# Connectors.net
KiCad netlist of a schematic drawn in Altium Designer
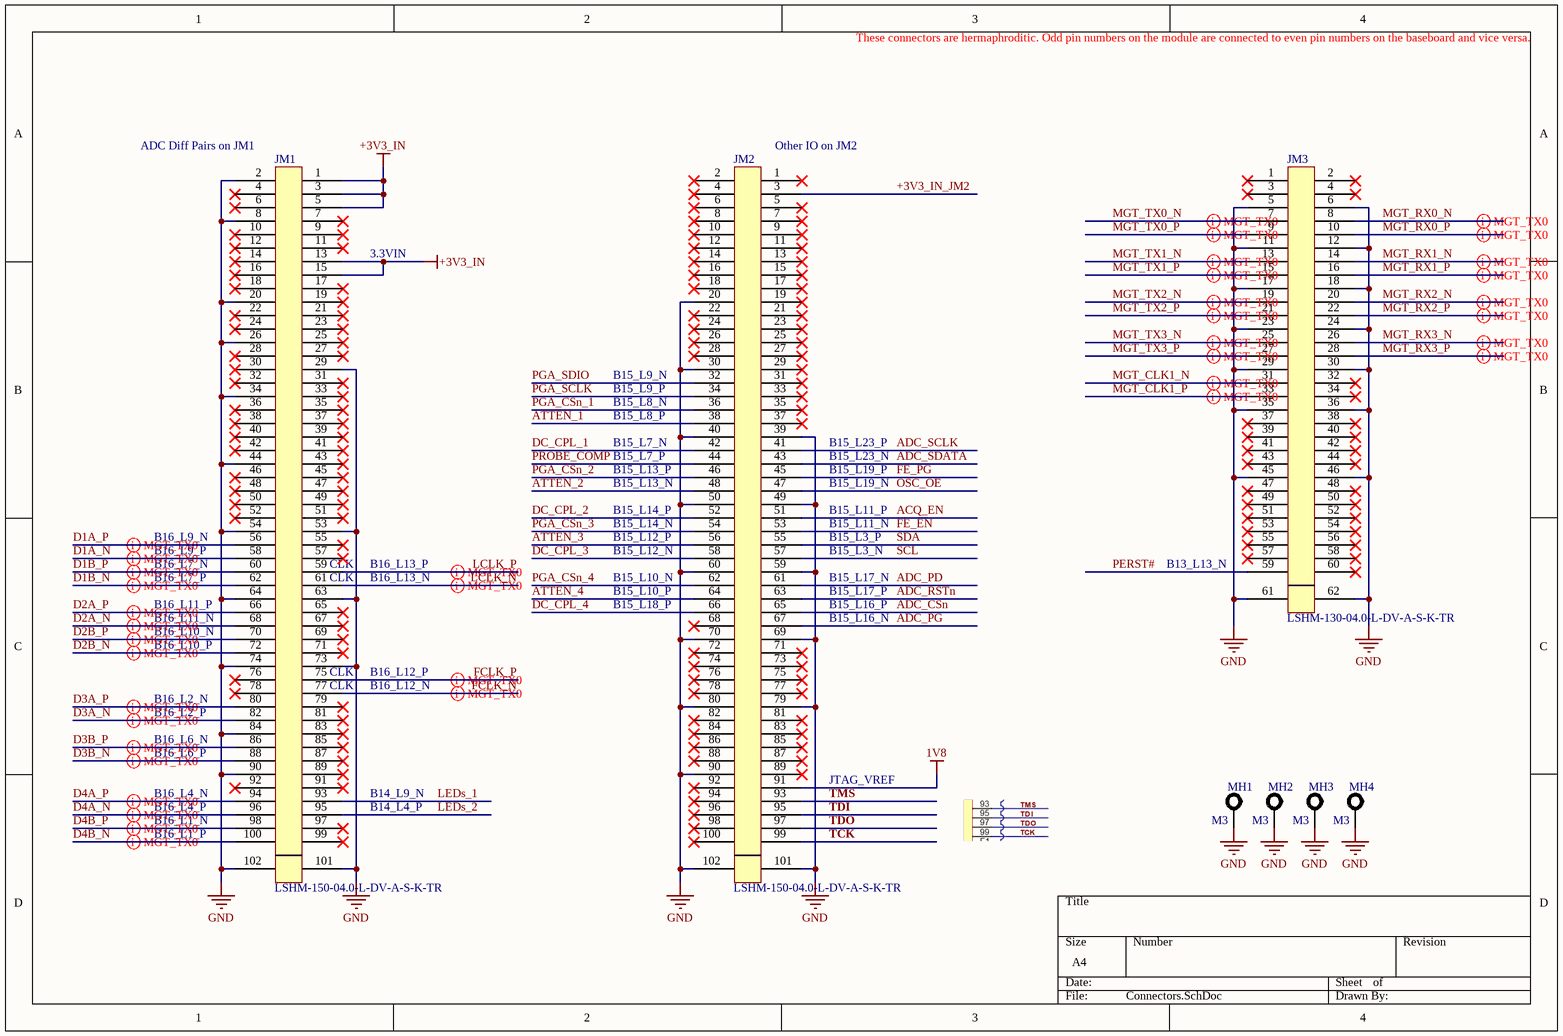
[diagram p0: Connectors.SchDoc]

(export (version "E")
  (design (tool "Eeschema 10.0.6"))
  (components
    (comp (ref "JM1")
      (value "LSHM-150-04.0-L-DV-A-S-K-TR")
      (footprint "SAM_LSHM-150-XX.X-XX-DV-A-S")
      (libsource (lib "DSO") (part "CONN LSHM-150-04.0-L-DV-A-S-K-TR"))
    )
    (comp (ref "JM2")
      (value "LSHM-150-04.0-L-DV-A-S-K-TR")
      (footprint "SAM_LSHM-150-XX.X-XX-DV-A-S")
      (libsource (lib "DSO") (part "CONN LSHM-150-04.0-L-DV-A-S-K-TR"))
    )
    (comp (ref "JM3")
      (value "LSHM-130-04.0-L-DV-A-S-K-TR")
      (footprint "SAM_LSHM-130-XX.X-XX-DV-A-S")
      (libsource (lib "DSO") (part "CONN LSHM-130-04.0-L-DV-A-S-K-TR"))
    )
    (comp (ref "MH1") (value "M3") (footprint "MH M3") (libsource (lib "DSO") (part "MH M3")))
    (comp (ref "MH2") (value "M3") (footprint "MH M3") (libsource (lib "DSO") (part "MH M3")))
    (comp (ref "MH3") (value "M3") (footprint "MH M3") (libsource (lib "DSO") (part "MH M3")))
    (comp (ref "MH4") (value "M3") (footprint "MH M3") (libsource (lib "DSO") (part "MH M3")))
  )
  (nets
    (net (code "1") (name "+3V3_IN") (class "Default")
      (node (ref "JM1") (pin "1") (pinfunction "1_1") (pintype "passive"))
      (node (ref "JM1") (pin "13") (pinfunction "13_13") (pintype "passive"))
      (node (ref "JM1") (pin "15") (pinfunction "15_15") (pintype "passive"))
      (node (ref "JM1") (pin "3") (pinfunction "3_3") (pintype "passive"))
      (node (ref "JM1") (pin "5") (pinfunction "5_5") (pintype "passive"))
    )
    (net (code "2") (name "/+3V3_IN_JM2") (class "Default")
      (node (ref "JM2") (pin "3") (pinfunction "3_3") (pintype "passive"))
    )
    (net (code "3") (name "/ACQ_EN") (class "Default")
      (node (ref "JM2") (pin "51") (pinfunction "51_51") (pintype "passive"))
    )
    (net (code "4") (name "/ADC_CSn") (class "Default")
      (node (ref "JM2") (pin "65") (pinfunction "65_65") (pintype "passive"))
    )
    (net (code "5") (name "/ADC_PD") (class "Default")
      (node (ref "JM2") (pin "61") (pinfunction "61_61") (pintype "passive"))
    )
    (net (code "6") (name "/ADC_PG") (class "Default")
      (node (ref "JM2") (pin "67") (pinfunction "67_67") (pintype "passive"))
    )
    (net (code "7") (name "/ADC_RSTn") (class "Default")
      (node (ref "JM2") (pin "63") (pinfunction "63_63") (pintype "passive"))
    )
    (net (code "8") (name "/ADC_SCLK") (class "Default")
      (node (ref "JM2") (pin "41") (pinfunction "41_41") (pintype "passive"))
    )
    (net (code "9") (name "/ADC_SDATA") (class "Default")
      (node (ref "JM2") (pin "43") (pinfunction "43_43") (pintype "passive"))
    )
    (net (code "10") (name "/ATTEN_1") (class "Default")
      (node (ref "JM2") (pin "38") (pinfunction "38_38") (pintype "passive"))
    )
    (net (code "11") (name "/ATTEN_2") (class "Default")
      (node (ref "JM2") (pin "48") (pinfunction "48_48") (pintype "passive"))
    )
    (net (code "12") (name "/ATTEN_3") (class "Default")
      (node (ref "JM2") (pin "56") (pinfunction "56_56") (pintype "passive"))
    )
    (net (code "13") (name "/ATTEN_4") (class "Default")
      (node (ref "JM2") (pin "64") (pinfunction "64_64") (pintype "passive"))
    )
    (net (code "14") (name "/D1A_N") (class "Default")
      (node (ref "JM1") (pin "58") (pinfunction "58_58") (pintype "passive"))
    )
    (net (code "15") (name "/D1A_P") (class "Default")
      (node (ref "JM1") (pin "56") (pinfunction "56_56") (pintype "passive"))
    )
    (net (code "16") (name "/D1B_N") (class "Default")
      (node (ref "JM1") (pin "62") (pinfunction "62_62") (pintype "passive"))
    )
    (net (code "17") (name "/D1B_P") (class "Default")
      (node (ref "JM1") (pin "60") (pinfunction "60_60") (pintype "passive"))
    )
    (net (code "18") (name "/D2A_N") (class "Default")
      (node (ref "JM1") (pin "68") (pinfunction "68_68") (pintype "passive"))
    )
    (net (code "19") (name "/D2A_P") (class "Default")
      (node (ref "JM1") (pin "66") (pinfunction "66_66") (pintype "passive"))
    )
    (net (code "20") (name "/D2B_N") (class "Default")
      (node (ref "JM1") (pin "72") (pinfunction "72_72") (pintype "passive"))
    )
    (net (code "21") (name "/D2B_P") (class "Default")
      (node (ref "JM1") (pin "70") (pinfunction "70_70") (pintype "passive"))
    )
    (net (code "22") (name "/D3A_N") (class "Default")
      (node (ref "JM1") (pin "82") (pinfunction "82_82") (pintype "passive"))
    )
    (net (code "23") (name "/D3A_P") (class "Default")
      (node (ref "JM1") (pin "80") (pinfunction "80_80") (pintype "passive"))
    )
    (net (code "24") (name "/D3B_N") (class "Default")
      (node (ref "JM1") (pin "88") (pinfunction "88_88") (pintype "passive"))
    )
    (net (code "25") (name "/D3B_P") (class "Default")
      (node (ref "JM1") (pin "86") (pinfunction "86_86") (pintype "passive"))
    )
    (net (code "26") (name "/D4A_N") (class "Default")
      (node (ref "JM1") (pin "96") (pinfunction "96_96") (pintype "passive"))
    )
    (net (code "27") (name "/D4A_P") (class "Default")
      (node (ref "JM1") (pin "94") (pinfunction "94_94") (pintype "passive"))
    )
    (net (code "28") (name "/D4B_N") (class "Default")
      (node (ref "JM1") (pin "100") (pinfunction "100_100") (pintype "passive"))
    )
    (net (code "29") (name "/D4B_P") (class "Default")
      (node (ref "JM1") (pin "98") (pinfunction "98_98") (pintype "passive"))
    )
    (net (code "30") (name "/DC_CPL_1") (class "Default")
      (node (ref "JM2") (pin "42") (pinfunction "42_42") (pintype "passive"))
    )
    (net (code "31") (name "/DC_CPL_2") (class "Default")
      (node (ref "JM2") (pin "52") (pinfunction "52_52") (pintype "passive"))
    )
    (net (code "32") (name "/DC_CPL_3") (class "Default")
      (node (ref "JM2") (pin "58") (pinfunction "58_58") (pintype "passive"))
    )
    (net (code "33") (name "/DC_CPL_4") (class "Default")
      (node (ref "JM2") (pin "66") (pinfunction "66_66") (pintype "passive"))
    )
    (net (code "34") (name "/FCLK_N") (class "Default")
      (node (ref "JM1") (pin "77") (pinfunction "77_77") (pintype "passive"))
    )
    (net (code "35") (name "/FCLK_P") (class "Default")
      (node (ref "JM1") (pin "75") (pinfunction "75_75") (pintype "passive"))
    )
    (net (code "36") (name "/FE_EN") (class "Default")
      (node (ref "JM2") (pin "53") (pinfunction "53_53") (pintype "passive"))
    )
    (net (code "37") (name "/FE_PG") (class "Default")
      (node (ref "JM2") (pin "45") (pinfunction "45_45") (pintype "passive"))
    )
    (net (code "38") (name "/LCLK_N") (class "Default")
      (node (ref "JM1") (pin "61") (pinfunction "61_61") (pintype "passive"))
    )
    (net (code "39") (name "/LCLK_P") (class "Default")
      (node (ref "JM1") (pin "59") (pinfunction "59_59") (pintype "passive"))
    )
    (net (code "40") (name "/LEDs_1") (class "Default")
      (node (ref "JM1") (pin "93") (pinfunction "93_93") (pintype "passive"))
    )
    (net (code "41") (name "/LEDs_2") (class "Default")
      (node (ref "JM1") (pin "95") (pinfunction "95_95") (pintype "passive"))
    )
    (net (code "42") (name "/MGT_CLK1_N") (class "Default")
      (node (ref "JM3") (pin "31") (pinfunction "31_31") (pintype "passive"))
    )
    (net (code "43") (name "/MGT_CLK1_P") (class "Default")
      (node (ref "JM3") (pin "33") (pinfunction "33_33") (pintype "passive"))
    )
    (net (code "44") (name "/MGT_RX0_N") (class "Default")
      (node (ref "JM3") (pin "8") (pinfunction "8_8") (pintype "passive"))
    )
    (net (code "45") (name "/MGT_RX0_P") (class "Default")
      (node (ref "JM3") (pin "10") (pinfunction "10_10") (pintype "passive"))
    )
    (net (code "46") (name "/MGT_RX1_N") (class "Default")
      (node (ref "JM3") (pin "14") (pinfunction "14_14") (pintype "passive"))
    )
    (net (code "47") (name "/MGT_RX1_P") (class "Default")
      (node (ref "JM3") (pin "16") (pinfunction "16_16") (pintype "passive"))
    )
    (net (code "48") (name "/MGT_RX2_N") (class "Default")
      (node (ref "JM3") (pin "20") (pinfunction "20_20") (pintype "passive"))
    )
    (net (code "49") (name "/MGT_RX2_P") (class "Default")
      (node (ref "JM3") (pin "22") (pinfunction "22_22") (pintype "passive"))
    )
    (net (code "50") (name "/MGT_RX3_N") (class "Default")
      (node (ref "JM3") (pin "26") (pinfunction "26_26") (pintype "passive"))
    )
    (net (code "51") (name "/MGT_RX3_P") (class "Default")
      (node (ref "JM3") (pin "28") (pinfunction "28_28") (pintype "passive"))
    )
    (net (code "52") (name "/MGT_TX0_N") (class "Default")
      (node (ref "JM3") (pin "7") (pinfunction "7_7") (pintype "passive"))
    )
    (net (code "53") (name "/MGT_TX0_P") (class "Default")
      (node (ref "JM3") (pin "9") (pinfunction "9_9") (pintype "passive"))
    )
    (net (code "54") (name "/MGT_TX1_N") (class "Default")
      (node (ref "JM3") (pin "13") (pinfunction "13_13") (pintype "passive"))
    )
    (net (code "55") (name "/MGT_TX1_P") (class "Default")
      (node (ref "JM3") (pin "15") (pinfunction "15_15") (pintype "passive"))
    )
    (net (code "56") (name "/MGT_TX2_N") (class "Default")
      (node (ref "JM3") (pin "19") (pinfunction "19_19") (pintype "passive"))
    )
    (net (code "57") (name "/MGT_TX2_P") (class "Default")
      (node (ref "JM3") (pin "21") (pinfunction "21_21") (pintype "passive"))
    )
    (net (code "58") (name "/MGT_TX3_N") (class "Default")
      (node (ref "JM3") (pin "25") (pinfunction "25_25") (pintype "passive"))
    )
    (net (code "59") (name "/MGT_TX3_P") (class "Default")
      (node (ref "JM3") (pin "27") (pinfunction "27_27") (pintype "passive"))
    )
    (net (code "60") (name "/OSC_OE") (class "Default")
      (node (ref "JM2") (pin "47") (pinfunction "47_47") (pintype "passive"))
    )
    (net (code "61") (name "/PERST#") (class "Default")
      (node (ref "JM3") (pin "59") (pinfunction "59_59") (pintype "passive"))
    )
    (net (code "62") (name "/PGA_CSn_1") (class "Default")
      (node (ref "JM2") (pin "36") (pinfunction "36_36") (pintype "passive"))
    )
    (net (code "63") (name "/PGA_CSn_2") (class "Default")
      (node (ref "JM2") (pin "46") (pinfunction "46_46") (pintype "passive"))
    )
    (net (code "64") (name "/PGA_CSn_3") (class "Default")
      (node (ref "JM2") (pin "54") (pinfunction "54_54") (pintype "passive"))
    )
    (net (code "65") (name "/PGA_CSn_4") (class "Default")
      (node (ref "JM2") (pin "62") (pinfunction "62_62") (pintype "passive"))
    )
    (net (code "66") (name "/PGA_SCLK") (class "Default")
      (node (ref "JM2") (pin "34") (pinfunction "34_34") (pintype "passive"))
    )
    (net (code "67") (name "/PGA_SDIO") (class "Default")
      (node (ref "JM2") (pin "32") (pinfunction "32_32") (pintype "passive"))
    )
    (net (code "68") (name "/PROBE_COMP") (class "Default")
      (node (ref "JM2") (pin "44") (pinfunction "44_44") (pintype "passive"))
    )
    (net (code "69") (name "/SCL") (class "Default")
      (node (ref "JM2") (pin "57") (pinfunction "57_57") (pintype "passive"))
    )
    (net (code "70") (name "/SDA") (class "Default")
      (node (ref "JM2") (pin "55") (pinfunction "55_55") (pintype "passive"))
    )
    (net (code "71") (name "/TCK") (class "Default")
      (node (ref "JM2") (pin "99") (pinfunction "99_99") (pintype "passive"))
    )
    (net (code "72") (name "/TDI") (class "Default")
      (node (ref "JM2") (pin "95") (pinfunction "95_95") (pintype "passive"))
    )
    (net (code "73") (name "/TDO") (class "Default")
      (node (ref "JM2") (pin "97") (pinfunction "97_97") (pintype "passive"))
    )
    (net (code "74") (name "/TMS") (class "Default")
      (node (ref "JM2") (pin "93") (pinfunction "93_93") (pintype "passive"))
    )
    (net (code "75") (name "1V8") (class "Default")
      (node (ref "JM2") (pin "91") (pinfunction "91_91") (pintype "passive"))
    )
    (net (code "76") (name "GND") (class "Default")
      (node (ref "JM1") (pin "101") (pinfunction "101_101") (pintype "passive"))
      (node (ref "JM1") (pin "102") (pinfunction "102_102") (pintype "passive"))
      (node (ref "JM1") (pin "2") (pinfunction "2_2") (pintype "passive"))
      (node (ref "JM1") (pin "20") (pinfunction "20_20") (pintype "passive"))
      (node (ref "JM1") (pin "26") (pinfunction "26_26") (pintype "passive"))
      (node (ref "JM1") (pin "29") (pinfunction "29_29") (pintype "passive"))
      (node (ref "JM1") (pin "34") (pinfunction "34_34") (pintype "passive"))
      (node (ref "JM1") (pin "44") (pinfunction "44_44") (pintype "passive"))
      (node (ref "JM1") (pin "53") (pinfunction "53_53") (pintype "passive"))
      (node (ref "JM1") (pin "54") (pinfunction "54_54") (pintype "passive"))
      (node (ref "JM1") (pin "63") (pinfunction "63_63") (pintype "passive"))
      (node (ref "JM1") (pin "64") (pinfunction "64_64") (pintype "passive"))
      (node (ref "JM1") (pin "73") (pinfunction "73_73") (pintype "passive"))
      (node (ref "JM1") (pin "74") (pinfunction "74_74") (pintype "passive"))
      (node (ref "JM1") (pin "8") (pinfunction "8_8") (pintype "passive"))
      (node (ref "JM1") (pin "84") (pinfunction "84_84") (pintype "passive"))
      (node (ref "JM1") (pin "90") (pinfunction "90_90") (pintype "passive"))
      (node (ref "JM2") (pin "101") (pinfunction "101_101") (pintype "passive"))
      (node (ref "JM2") (pin "102") (pinfunction "102_102") (pintype "passive"))
      (node (ref "JM2") (pin "20") (pinfunction "20_20") (pintype "passive"))
      (node (ref "JM2") (pin "30") (pinfunction "30_30") (pintype "passive"))
      (node (ref "JM2") (pin "39") (pinfunction "39_39") (pintype "passive"))
      (node (ref "JM2") (pin "40") (pinfunction "40_40") (pintype "passive"))
      (node (ref "JM2") (pin "49") (pinfunction "49_49") (pintype "passive"))
      (node (ref "JM2") (pin "50") (pinfunction "50_50") (pintype "passive"))
      (node (ref "JM2") (pin "59") (pinfunction "59_59") (pintype "passive"))
      (node (ref "JM2") (pin "60") (pinfunction "60_60") (pintype "passive"))
      (node (ref "JM2") (pin "69") (pinfunction "69_69") (pintype "passive"))
      (node (ref "JM2") (pin "70") (pinfunction "70_70") (pintype "passive"))
      (node (ref "JM2") (pin "79") (pinfunction "79_79") (pintype "passive"))
      (node (ref "JM2") (pin "80") (pinfunction "80_80") (pintype "passive"))
      (node (ref "JM2") (pin "90") (pinfunction "90_90") (pintype "passive"))
      (node (ref "JM3") (pin "11") (pinfunction "11_11") (pintype "passive"))
      (node (ref "JM3") (pin "12") (pinfunction "12_12") (pintype "passive"))
      (node (ref "JM3") (pin "17") (pinfunction "17_17") (pintype "passive"))
      (node (ref "JM3") (pin "18") (pinfunction "18_18") (pintype "passive"))
      (node (ref "JM3") (pin "23") (pinfunction "23_23") (pintype "passive"))
      (node (ref "JM3") (pin "24") (pinfunction "24_24") (pintype "passive"))
      (node (ref "JM3") (pin "29") (pinfunction "29_29") (pintype "passive"))
      (node (ref "JM3") (pin "30") (pinfunction "30_30") (pintype "passive"))
      (node (ref "JM3") (pin "35") (pinfunction "35_35") (pintype "passive"))
      (node (ref "JM3") (pin "36") (pinfunction "36_36") (pintype "passive"))
      (node (ref "JM3") (pin "45") (pinfunction "45_45") (pintype "passive"))
      (node (ref "JM3") (pin "46") (pinfunction "46_46") (pintype "passive"))
      (node (ref "JM3") (pin "5") (pinfunction "5_5") (pintype "passive"))
      (node (ref "JM3") (pin "6") (pinfunction "6_6") (pintype "passive"))
      (node (ref "JM3") (pin "61") (pinfunction "61_61") (pintype "passive"))
      (node (ref "JM3") (pin "62") (pinfunction "62_62") (pintype "passive"))
      (node (ref "MH1") (pin "1") (pinfunction "1_1") (pintype "passive"))
      (node (ref "MH2") (pin "1") (pinfunction "1_1") (pintype "passive"))
      (node (ref "MH3") (pin "1") (pinfunction "1_1") (pintype "passive"))
      (node (ref "MH4") (pin "1") (pinfunction "1_1") (pintype "passive"))
    )
    (net (code "77") (name "unconnected-(JM1-Pad4)") (class "Default")
      (node (ref "JM1") (pin "4") (pinfunction "4_4") (pintype "passive+no_connect"))
    )
    (net (code "78") (name "unconnected-(JM1-Pad6)") (class "Default")
      (node (ref "JM1") (pin "6") (pinfunction "6_6") (pintype "passive+no_connect"))
    )
    (net (code "79") (name "unconnected-(JM1-Pad7)") (class "Default")
      (node (ref "JM1") (pin "7") (pinfunction "7_7") (pintype "passive+no_connect"))
    )
    (net (code "80") (name "unconnected-(JM1-Pad9)") (class "Default")
      (node (ref "JM1") (pin "9") (pinfunction "9_9") (pintype "passive+no_connect"))
    )
    (net (code "81") (name "unconnected-(JM1-Pad10)") (class "Default")
      (node (ref "JM1") (pin "10") (pinfunction "10_10") (pintype "passive+no_connect"))
    )
    (net (code "82") (name "unconnected-(JM1-Pad11)") (class "Default")
      (node (ref "JM1") (pin "11") (pinfunction "11_11") (pintype "passive+no_connect"))
    )
    (net (code "83") (name "unconnected-(JM1-Pad12)") (class "Default")
      (node (ref "JM1") (pin "12") (pinfunction "12_12") (pintype "passive+no_connect"))
    )
    (net (code "84") (name "unconnected-(JM1-Pad14)") (class "Default")
      (node (ref "JM1") (pin "14") (pinfunction "14_14") (pintype "passive+no_connect"))
    )
    (net (code "85") (name "unconnected-(JM1-Pad16)") (class "Default")
      (node (ref "JM1") (pin "16") (pinfunction "16_16") (pintype "passive+no_connect"))
    )
    (net (code "86") (name "unconnected-(JM1-Pad17)") (class "Default")
      (node (ref "JM1") (pin "17") (pinfunction "17_17") (pintype "passive+no_connect"))
    )
    (net (code "87") (name "unconnected-(JM1-Pad18)") (class "Default")
      (node (ref "JM1") (pin "18") (pinfunction "18_18") (pintype "passive+no_connect"))
    )
    (net (code "88") (name "unconnected-(JM1-Pad19)") (class "Default")
      (node (ref "JM1") (pin "19") (pinfunction "19_19") (pintype "passive+no_connect"))
    )
    (net (code "89") (name "unconnected-(JM1-Pad21)") (class "Default")
      (node (ref "JM1") (pin "21") (pinfunction "21_21") (pintype "passive+no_connect"))
    )
    (net (code "90") (name "unconnected-(JM1-Pad22)") (class "Default")
      (node (ref "JM1") (pin "22") (pinfunction "22_22") (pintype "passive+no_connect"))
    )
    (net (code "91") (name "unconnected-(JM1-Pad23)") (class "Default")
      (node (ref "JM1") (pin "23") (pinfunction "23_23") (pintype "passive+no_connect"))
    )
    (net (code "92") (name "unconnected-(JM1-Pad24)") (class "Default")
      (node (ref "JM1") (pin "24") (pinfunction "24_24") (pintype "passive+no_connect"))
    )
    (net (code "93") (name "unconnected-(JM1-Pad25)") (class "Default")
      (node (ref "JM1") (pin "25") (pinfunction "25_25") (pintype "passive+no_connect"))
    )
    (net (code "94") (name "unconnected-(JM1-Pad27)") (class "Default")
      (node (ref "JM1") (pin "27") (pinfunction "27_27") (pintype "passive+no_connect"))
    )
    (net (code "95") (name "unconnected-(JM1-Pad28)") (class "Default")
      (node (ref "JM1") (pin "28") (pinfunction "28_28") (pintype "passive+no_connect"))
    )
    (net (code "96") (name "unconnected-(JM1-Pad30)") (class "Default")
      (node (ref "JM1") (pin "30") (pinfunction "30_30") (pintype "passive+no_connect"))
    )
    (net (code "97") (name "unconnected-(JM1-Pad31)") (class "Default")
      (node (ref "JM1") (pin "31") (pinfunction "31_31") (pintype "passive+no_connect"))
    )
    (net (code "98") (name "unconnected-(JM1-Pad32)") (class "Default")
      (node (ref "JM1") (pin "32") (pinfunction "32_32") (pintype "passive+no_connect"))
    )
    (net (code "99") (name "unconnected-(JM1-Pad33)") (class "Default")
      (node (ref "JM1") (pin "33") (pinfunction "33_33") (pintype "passive+no_connect"))
    )
    (net (code "100") (name "unconnected-(JM1-Pad35)") (class "Default")
      (node (ref "JM1") (pin "35") (pinfunction "35_35") (pintype "passive+no_connect"))
    )
    (net (code "101") (name "unconnected-(JM1-Pad36)") (class "Default")
      (node (ref "JM1") (pin "36") (pinfunction "36_36") (pintype "passive+no_connect"))
    )
    (net (code "102") (name "unconnected-(JM1-Pad37)") (class "Default")
      (node (ref "JM1") (pin "37") (pinfunction "37_37") (pintype "passive+no_connect"))
    )
    (net (code "103") (name "unconnected-(JM1-Pad38)") (class "Default")
      (node (ref "JM1") (pin "38") (pinfunction "38_38") (pintype "passive+no_connect"))
    )
    (net (code "104") (name "unconnected-(JM1-Pad39)") (class "Default")
      (node (ref "JM1") (pin "39") (pinfunction "39_39") (pintype "passive+no_connect"))
    )
    (net (code "105") (name "unconnected-(JM1-Pad40)") (class "Default")
      (node (ref "JM1") (pin "40") (pinfunction "40_40") (pintype "passive+no_connect"))
    )
    (net (code "106") (name "unconnected-(JM1-Pad41)") (class "Default")
      (node (ref "JM1") (pin "41") (pinfunction "41_41") (pintype "passive+no_connect"))
    )
    (net (code "107") (name "unconnected-(JM1-Pad42)") (class "Default")
      (node (ref "JM1") (pin "42") (pinfunction "42_42") (pintype "passive+no_connect"))
    )
    (net (code "108") (name "unconnected-(JM1-Pad43)") (class "Default")
      (node (ref "JM1") (pin "43") (pinfunction "43_43") (pintype "passive+no_connect"))
    )
    (net (code "109") (name "unconnected-(JM1-Pad45)") (class "Default")
      (node (ref "JM1") (pin "45") (pinfunction "45_45") (pintype "passive+no_connect"))
    )
    (net (code "110") (name "unconnected-(JM1-Pad46)") (class "Default")
      (node (ref "JM1") (pin "46") (pinfunction "46_46") (pintype "passive+no_connect"))
    )
    (net (code "111") (name "unconnected-(JM1-Pad47)") (class "Default")
      (node (ref "JM1") (pin "47") (pinfunction "47_47") (pintype "passive+no_connect"))
    )
    (net (code "112") (name "unconnected-(JM1-Pad48)") (class "Default")
      (node (ref "JM1") (pin "48") (pinfunction "48_48") (pintype "passive+no_connect"))
    )
    (net (code "113") (name "unconnected-(JM1-Pad49)") (class "Default")
      (node (ref "JM1") (pin "49") (pinfunction "49_49") (pintype "passive+no_connect"))
    )
    (net (code "114") (name "unconnected-(JM1-Pad50)") (class "Default")
      (node (ref "JM1") (pin "50") (pinfunction "50_50") (pintype "passive+no_connect"))
    )
    (net (code "115") (name "unconnected-(JM1-Pad51)") (class "Default")
      (node (ref "JM1") (pin "51") (pinfunction "51_51") (pintype "passive+no_connect"))
    )
    (net (code "116") (name "unconnected-(JM1-Pad52)") (class "Default")
      (node (ref "JM1") (pin "52") (pinfunction "52_52") (pintype "passive+no_connect"))
    )
    (net (code "117") (name "unconnected-(JM1-Pad55)") (class "Default")
      (node (ref "JM1") (pin "55") (pinfunction "55_55") (pintype "passive+no_connect"))
    )
    (net (code "118") (name "unconnected-(JM1-Pad57)") (class "Default")
      (node (ref "JM1") (pin "57") (pinfunction "57_57") (pintype "passive+no_connect"))
    )
    (net (code "119") (name "unconnected-(JM1-Pad65)") (class "Default")
      (node (ref "JM1") (pin "65") (pinfunction "65_65") (pintype "passive+no_connect"))
    )
    (net (code "120") (name "unconnected-(JM1-Pad67)") (class "Default")
      (node (ref "JM1") (pin "67") (pinfunction "67_67") (pintype "passive+no_connect"))
    )
    (net (code "121") (name "unconnected-(JM1-Pad69)") (class "Default")
      (node (ref "JM1") (pin "69") (pinfunction "69_69") (pintype "passive+no_connect"))
    )
    (net (code "122") (name "unconnected-(JM1-Pad71)") (class "Default")
      (node (ref "JM1") (pin "71") (pinfunction "71_71") (pintype "passive+no_connect"))
    )
    (net (code "123") (name "unconnected-(JM1-Pad76)") (class "Default")
      (node (ref "JM1") (pin "76") (pinfunction "76_76") (pintype "passive+no_connect"))
    )
    (net (code "124") (name "unconnected-(JM1-Pad78)") (class "Default")
      (node (ref "JM1") (pin "78") (pinfunction "78_78") (pintype "passive+no_connect"))
    )
    (net (code "125") (name "unconnected-(JM1-Pad79)") (class "Default")
      (node (ref "JM1") (pin "79") (pinfunction "79_79") (pintype "passive+no_connect"))
    )
    (net (code "126") (name "unconnected-(JM1-Pad81)") (class "Default")
      (node (ref "JM1") (pin "81") (pinfunction "81_81") (pintype "passive+no_connect"))
    )
    (net (code "127") (name "unconnected-(JM1-Pad83)") (class "Default")
      (node (ref "JM1") (pin "83") (pinfunction "83_83") (pintype "passive+no_connect"))
    )
    (net (code "128") (name "unconnected-(JM1-Pad85)") (class "Default")
      (node (ref "JM1") (pin "85") (pinfunction "85_85") (pintype "passive+no_connect"))
    )
    (net (code "129") (name "unconnected-(JM1-Pad87)") (class "Default")
      (node (ref "JM1") (pin "87") (pinfunction "87_87") (pintype "passive+no_connect"))
    )
    (net (code "130") (name "unconnected-(JM1-Pad89)") (class "Default")
      (node (ref "JM1") (pin "89") (pinfunction "89_89") (pintype "passive+no_connect"))
    )
    (net (code "131") (name "unconnected-(JM1-Pad91)") (class "Default")
      (node (ref "JM1") (pin "91") (pinfunction "91_91") (pintype "passive+no_connect"))
    )
    (net (code "132") (name "unconnected-(JM1-Pad92)") (class "Default")
      (node (ref "JM1") (pin "92") (pinfunction "92_92") (pintype "passive+no_connect"))
    )
    (net (code "133") (name "unconnected-(JM1-Pad97)") (class "Default")
      (node (ref "JM1") (pin "97") (pinfunction "97_97") (pintype "passive+no_connect"))
    )
    (net (code "134") (name "unconnected-(JM1-Pad99)") (class "Default")
      (node (ref "JM1") (pin "99") (pinfunction "99_99") (pintype "passive+no_connect"))
    )
    (net (code "135") (name "unconnected-(JM2-Pad1)") (class "Default")
      (node (ref "JM2") (pin "1") (pinfunction "1_1") (pintype "passive+no_connect"))
    )
    (net (code "136") (name "unconnected-(JM2-Pad2)") (class "Default")
      (node (ref "JM2") (pin "2") (pinfunction "2_2") (pintype "passive+no_connect"))
    )
    (net (code "137") (name "unconnected-(JM2-Pad4)") (class "Default")
      (node (ref "JM2") (pin "4") (pinfunction "4_4") (pintype "passive+no_connect"))
    )
    (net (code "138") (name "unconnected-(JM2-Pad5)") (class "Default")
      (node (ref "JM2") (pin "5") (pinfunction "5_5") (pintype "passive+no_connect"))
    )
    (net (code "139") (name "unconnected-(JM2-Pad6)") (class "Default")
      (node (ref "JM2") (pin "6") (pinfunction "6_6") (pintype "passive+no_connect"))
    )
    (net (code "140") (name "unconnected-(JM2-Pad7)") (class "Default")
      (node (ref "JM2") (pin "7") (pinfunction "7_7") (pintype "passive+no_connect"))
    )
    (net (code "141") (name "unconnected-(JM2-Pad8)") (class "Default")
      (node (ref "JM2") (pin "8") (pinfunction "8_8") (pintype "passive+no_connect"))
    )
    (net (code "142") (name "unconnected-(JM2-Pad9)") (class "Default")
      (node (ref "JM2") (pin "9") (pinfunction "9_9") (pintype "passive+no_connect"))
    )
    (net (code "143") (name "unconnected-(JM2-Pad10)") (class "Default")
      (node (ref "JM2") (pin "10") (pinfunction "10_10") (pintype "passive+no_connect"))
    )
    (net (code "144") (name "unconnected-(JM2-Pad11)") (class "Default")
      (node (ref "JM2") (pin "11") (pinfunction "11_11") (pintype "passive+no_connect"))
    )
    (net (code "145") (name "unconnected-(JM2-Pad12)") (class "Default")
      (node (ref "JM2") (pin "12") (pinfunction "12_12") (pintype "passive+no_connect"))
    )
    (net (code "146") (name "unconnected-(JM2-Pad13)") (class "Default")
      (node (ref "JM2") (pin "13") (pinfunction "13_13") (pintype "passive+no_connect"))
    )
    (net (code "147") (name "unconnected-(JM2-Pad14)") (class "Default")
      (node (ref "JM2") (pin "14") (pinfunction "14_14") (pintype "passive+no_connect"))
    )
    (net (code "148") (name "unconnected-(JM2-Pad15)") (class "Default")
      (node (ref "JM2") (pin "15") (pinfunction "15_15") (pintype "passive+no_connect"))
    )
    (net (code "149") (name "unconnected-(JM2-Pad16)") (class "Default")
      (node (ref "JM2") (pin "16") (pinfunction "16_16") (pintype "passive+no_connect"))
    )
    (net (code "150") (name "unconnected-(JM2-Pad17)") (class "Default")
      (node (ref "JM2") (pin "17") (pinfunction "17_17") (pintype "passive+no_connect"))
    )
    (net (code "151") (name "unconnected-(JM2-Pad18)") (class "Default")
      (node (ref "JM2") (pin "18") (pinfunction "18_18") (pintype "passive+no_connect"))
    )
    (net (code "152") (name "unconnected-(JM2-Pad19)") (class "Default")
      (node (ref "JM2") (pin "19") (pinfunction "19_19") (pintype "passive+no_connect"))
    )
    (net (code "153") (name "unconnected-(JM2-Pad21)") (class "Default")
      (node (ref "JM2") (pin "21") (pinfunction "21_21") (pintype "passive+no_connect"))
    )
    (net (code "154") (name "unconnected-(JM2-Pad22)") (class "Default")
      (node (ref "JM2") (pin "22") (pinfunction "22_22") (pintype "passive+no_connect"))
    )
    (net (code "155") (name "unconnected-(JM2-Pad23)") (class "Default")
      (node (ref "JM2") (pin "23") (pinfunction "23_23") (pintype "passive+no_connect"))
    )
    (net (code "156") (name "unconnected-(JM2-Pad24)") (class "Default")
      (node (ref "JM2") (pin "24") (pinfunction "24_24") (pintype "passive+no_connect"))
    )
    (net (code "157") (name "unconnected-(JM2-Pad25)") (class "Default")
      (node (ref "JM2") (pin "25") (pinfunction "25_25") (pintype "passive+no_connect"))
    )
    (net (code "158") (name "unconnected-(JM2-Pad26)") (class "Default")
      (node (ref "JM2") (pin "26") (pinfunction "26_26") (pintype "passive+no_connect"))
    )
    (net (code "159") (name "unconnected-(JM2-Pad27)") (class "Default")
      (node (ref "JM2") (pin "27") (pinfunction "27_27") (pintype "passive+no_connect"))
    )
    (net (code "160") (name "unconnected-(JM2-Pad28)") (class "Default")
      (node (ref "JM2") (pin "28") (pinfunction "28_28") (pintype "passive+no_connect"))
    )
    (net (code "161") (name "unconnected-(JM2-Pad29)") (class "Default")
      (node (ref "JM2") (pin "29") (pinfunction "29_29") (pintype "passive+no_connect"))
    )
    (net (code "162") (name "unconnected-(JM2-Pad31)") (class "Default")
      (node (ref "JM2") (pin "31") (pinfunction "31_31") (pintype "passive+no_connect"))
    )
    (net (code "163") (name "unconnected-(JM2-Pad33)") (class "Default")
      (node (ref "JM2") (pin "33") (pinfunction "33_33") (pintype "passive+no_connect"))
    )
    (net (code "164") (name "unconnected-(JM2-Pad35)") (class "Default")
      (node (ref "JM2") (pin "35") (pinfunction "35_35") (pintype "passive+no_connect"))
    )
    (net (code "165") (name "unconnected-(JM2-Pad37)") (class "Default")
      (node (ref "JM2") (pin "37") (pinfunction "37_37") (pintype "passive+no_connect"))
    )
    (net (code "166") (name "unconnected-(JM2-Pad68)") (class "Default")
      (node (ref "JM2") (pin "68") (pinfunction "68_68") (pintype "passive+no_connect"))
    )
    (net (code "167") (name "unconnected-(JM2-Pad71)") (class "Default")
      (node (ref "JM2") (pin "71") (pinfunction "71_71") (pintype "passive+no_connect"))
    )
    (net (code "168") (name "unconnected-(JM2-Pad72)") (class "Default")
      (node (ref "JM2") (pin "72") (pinfunction "72_72") (pintype "passive+no_connect"))
    )
    (net (code "169") (name "unconnected-(JM2-Pad73)") (class "Default")
      (node (ref "JM2") (pin "73") (pinfunction "73_73") (pintype "passive+no_connect"))
    )
    (net (code "170") (name "unconnected-(JM2-Pad74)") (class "Default")
      (node (ref "JM2") (pin "74") (pinfunction "74_74") (pintype "passive+no_connect"))
    )
    (net (code "171") (name "unconnected-(JM2-Pad75)") (class "Default")
      (node (ref "JM2") (pin "75") (pinfunction "75_75") (pintype "passive+no_connect"))
    )
    (net (code "172") (name "unconnected-(JM2-Pad76)") (class "Default")
      (node (ref "JM2") (pin "76") (pinfunction "76_76") (pintype "passive+no_connect"))
    )
    (net (code "173") (name "unconnected-(JM2-Pad77)") (class "Default")
      (node (ref "JM2") (pin "77") (pinfunction "77_77") (pintype "passive+no_connect"))
    )
    (net (code "174") (name "unconnected-(JM2-Pad78)") (class "Default")
      (node (ref "JM2") (pin "78") (pinfunction "78_78") (pintype "passive+no_connect"))
    )
    (net (code "175") (name "unconnected-(JM2-Pad81)") (class "Default")
      (node (ref "JM2") (pin "81") (pinfunction "81_81") (pintype "passive+no_connect"))
    )
    (net (code "176") (name "unconnected-(JM2-Pad82)") (class "Default")
      (node (ref "JM2") (pin "82") (pinfunction "82_82") (pintype "passive+no_connect"))
    )
    (net (code "177") (name "unconnected-(JM2-Pad83)") (class "Default")
      (node (ref "JM2") (pin "83") (pinfunction "83_83") (pintype "passive+no_connect"))
    )
    (net (code "178") (name "unconnected-(JM2-Pad84)") (class "Default")
      (node (ref "JM2") (pin "84") (pinfunction "84_84") (pintype "passive+no_connect"))
    )
    (net (code "179") (name "unconnected-(JM2-Pad85)") (class "Default")
      (node (ref "JM2") (pin "85") (pinfunction "85_85") (pintype "passive+no_connect"))
    )
    (net (code "180") (name "unconnected-(JM2-Pad86)") (class "Default")
      (node (ref "JM2") (pin "86") (pinfunction "86_86") (pintype "passive+no_connect"))
    )
    (net (code "181") (name "unconnected-(JM2-Pad87)") (class "Default")
      (node (ref "JM2") (pin "87") (pinfunction "87_87") (pintype "passive+no_connect"))
    )
    (net (code "182") (name "unconnected-(JM2-Pad88)") (class "Default")
      (node (ref "JM2") (pin "88") (pinfunction "88_88") (pintype "passive+no_connect"))
    )
    (net (code "183") (name "unconnected-(JM2-Pad89)") (class "Default")
      (node (ref "JM2") (pin "89") (pinfunction "89_89") (pintype "passive+no_connect"))
    )
    (net (code "184") (name "unconnected-(JM2-Pad92)") (class "Default")
      (node (ref "JM2") (pin "92") (pinfunction "92_92") (pintype "passive+no_connect"))
    )
    (net (code "185") (name "unconnected-(JM2-Pad94)") (class "Default")
      (node (ref "JM2") (pin "94") (pinfunction "94_94") (pintype "passive+no_connect"))
    )
    (net (code "186") (name "unconnected-(JM2-Pad96)") (class "Default")
      (node (ref "JM2") (pin "96") (pinfunction "96_96") (pintype "passive+no_connect"))
    )
    (net (code "187") (name "unconnected-(JM2-Pad98)") (class "Default")
      (node (ref "JM2") (pin "98") (pinfunction "98_98") (pintype "passive+no_connect"))
    )
    (net (code "188") (name "unconnected-(JM2-Pad100)") (class "Default")
      (node (ref "JM2") (pin "100") (pinfunction "100_100") (pintype "passive+no_connect"))
    )
    (net (code "189") (name "unconnected-(JM3-Pad1)") (class "Default")
      (node (ref "JM3") (pin "1") (pinfunction "1_1") (pintype "passive+no_connect"))
    )
    (net (code "190") (name "unconnected-(JM3-Pad2)") (class "Default")
      (node (ref "JM3") (pin "2") (pinfunction "2_2") (pintype "passive+no_connect"))
    )
    (net (code "191") (name "unconnected-(JM3-Pad3)") (class "Default")
      (node (ref "JM3") (pin "3") (pinfunction "3_3") (pintype "passive+no_connect"))
    )
    (net (code "192") (name "unconnected-(JM3-Pad4)") (class "Default")
      (node (ref "JM3") (pin "4") (pinfunction "4_4") (pintype "passive+no_connect"))
    )
    (net (code "193") (name "unconnected-(JM3-Pad32)") (class "Default")
      (node (ref "JM3") (pin "32") (pinfunction "32_32") (pintype "passive+no_connect"))
    )
    (net (code "194") (name "unconnected-(JM3-Pad34)") (class "Default")
      (node (ref "JM3") (pin "34") (pinfunction "34_34") (pintype "passive+no_connect"))
    )
    (net (code "195") (name "unconnected-(JM3-Pad37)") (class "Default")
      (node (ref "JM3") (pin "37") (pinfunction "37_37") (pintype "passive+no_connect"))
    )
    (net (code "196") (name "unconnected-(JM3-Pad38)") (class "Default")
      (node (ref "JM3") (pin "38") (pinfunction "38_38") (pintype "passive+no_connect"))
    )
    (net (code "197") (name "unconnected-(JM3-Pad39)") (class "Default")
      (node (ref "JM3") (pin "39") (pinfunction "39_39") (pintype "passive+no_connect"))
    )
    (net (code "198") (name "unconnected-(JM3-Pad40)") (class "Default")
      (node (ref "JM3") (pin "40") (pinfunction "40_40") (pintype "passive+no_connect"))
    )
    (net (code "199") (name "unconnected-(JM3-Pad41)") (class "Default")
      (node (ref "JM3") (pin "41") (pinfunction "41_41") (pintype "passive+no_connect"))
    )
    (net (code "200") (name "unconnected-(JM3-Pad42)") (class "Default")
      (node (ref "JM3") (pin "42") (pinfunction "42_42") (pintype "passive+no_connect"))
    )
    (net (code "201") (name "unconnected-(JM3-Pad43)") (class "Default")
      (node (ref "JM3") (pin "43") (pinfunction "43_43") (pintype "passive+no_connect"))
    )
    (net (code "202") (name "unconnected-(JM3-Pad44)") (class "Default")
      (node (ref "JM3") (pin "44") (pinfunction "44_44") (pintype "passive+no_connect"))
    )
    (net (code "203") (name "unconnected-(JM3-Pad47)") (class "Default")
      (node (ref "JM3") (pin "47") (pinfunction "47_47") (pintype "passive+no_connect"))
    )
    (net (code "204") (name "unconnected-(JM3-Pad48)") (class "Default")
      (node (ref "JM3") (pin "48") (pinfunction "48_48") (pintype "passive+no_connect"))
    )
    (net (code "205") (name "unconnected-(JM3-Pad49)") (class "Default")
      (node (ref "JM3") (pin "49") (pinfunction "49_49") (pintype "passive+no_connect"))
    )
    (net (code "206") (name "unconnected-(JM3-Pad50)") (class "Default")
      (node (ref "JM3") (pin "50") (pinfunction "50_50") (pintype "passive+no_connect"))
    )
    (net (code "207") (name "unconnected-(JM3-Pad51)") (class "Default")
      (node (ref "JM3") (pin "51") (pinfunction "51_51") (pintype "passive+no_connect"))
    )
    (net (code "208") (name "unconnected-(JM3-Pad52)") (class "Default")
      (node (ref "JM3") (pin "52") (pinfunction "52_52") (pintype "passive+no_connect"))
    )
    (net (code "209") (name "unconnected-(JM3-Pad53)") (class "Default")
      (node (ref "JM3") (pin "53") (pinfunction "53_53") (pintype "passive+no_connect"))
    )
    (net (code "210") (name "unconnected-(JM3-Pad54)") (class "Default")
      (node (ref "JM3") (pin "54") (pinfunction "54_54") (pintype "passive+no_connect"))
    )
    (net (code "211") (name "unconnected-(JM3-Pad55)") (class "Default")
      (node (ref "JM3") (pin "55") (pinfunction "55_55") (pintype "passive+no_connect"))
    )
    (net (code "212") (name "unconnected-(JM3-Pad56)") (class "Default")
      (node (ref "JM3") (pin "56") (pinfunction "56_56") (pintype "passive+no_connect"))
    )
    (net (code "213") (name "unconnected-(JM3-Pad57)") (class "Default")
      (node (ref "JM3") (pin "57") (pinfunction "57_57") (pintype "passive+no_connect"))
    )
    (net (code "214") (name "unconnected-(JM3-Pad58)") (class "Default")
      (node (ref "JM3") (pin "58") (pinfunction "58_58") (pintype "passive+no_connect"))
    )
    (net (code "215") (name "unconnected-(JM3-Pad60)") (class "Default")
      (node (ref "JM3") (pin "60") (pinfunction "60_60") (pintype "passive+no_connect"))
    )
  )
)
